# USB_PD_TYPE-C.net
KiCad netlist of a schematic drawn in Altium Designer
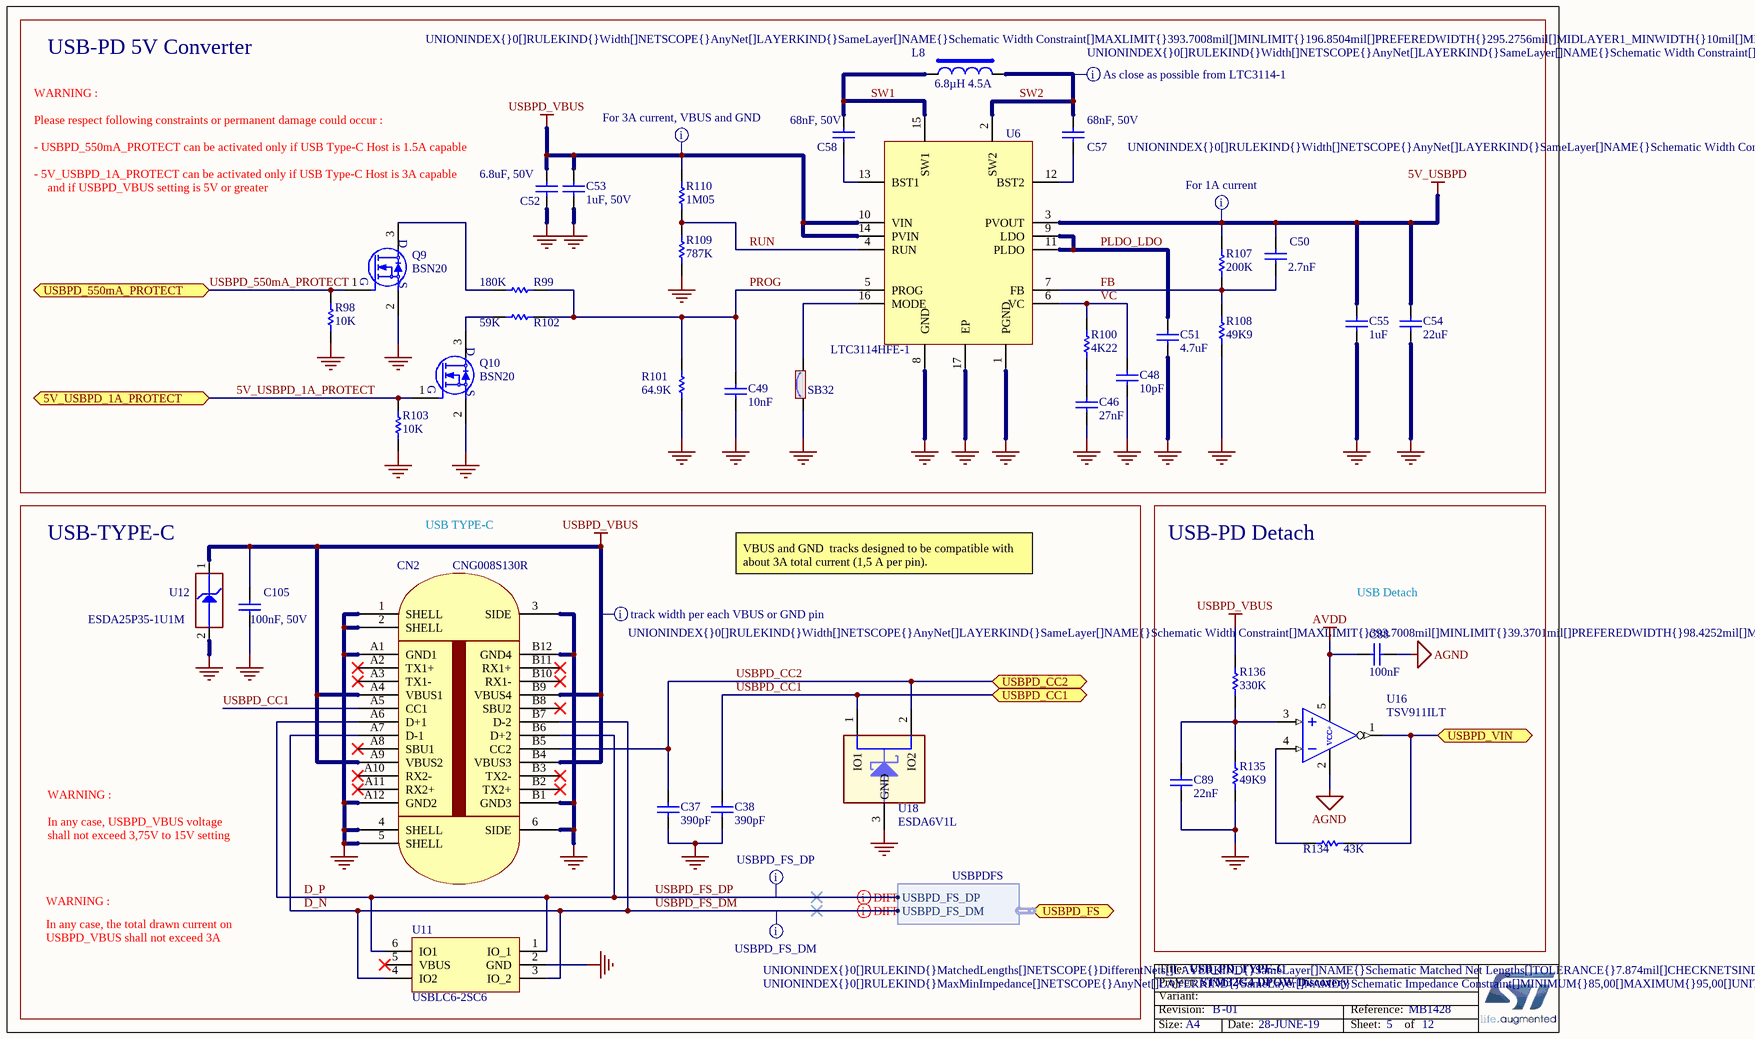
[diagram p0: USB_PD_TYPE-C.SchDoc]

(export (version "E")
  (design (tool "Eeschema 10.0.6"))
  (components
    (comp (ref "C37")
      (value "390pF")
      (footprint "C0402")
      (description "Capacitor, MLCC, 390pF, 50V, NPO, 5%, 0402, T=0,5mm")
      (fields
        (field (name "INTERNAL_PART_NUMBER") "MCD-01597")
        (field (name "MANUFACTURER_PART_NUMBER") "CC0402JRNPO9BN391")
        (field (name "PROVIDED_BY") "SUBCO")
      )
      (libsource (lib "MCD_PARTS_database") (part "Capacitor"))
    )
    (comp (ref "C38")
      (value "390pF")
      (footprint "C0402")
      (description "Capacitor, MLCC, 390pF, 50V, NPO, 5%, 0402, T=0,5mm")
      (fields
        (field (name "INTERNAL_PART_NUMBER") "MCD-01597")
        (field (name "MANUFACTURER_PART_NUMBER") "CC0402JRNPO9BN391")
        (field (name "PROVIDED_BY") "SUBCO")
      )
      (libsource (lib "MCD_PARTS_database") (part "Capacitor"))
    )
    (comp (ref "C46")
      (value "27nF")
      (footprint "C0805_KEMET_IPC-7351_DENSITY-LEVEL-B_H1P10")
      (description "Capacitor, MLCC, 27nF, 25V, C0G, 5%, 0805, T=1.1mm")
      (fields
        (field (name "INTERNAL_PART_NUMBER") "MCD-01719")
        (field (name "MANUFACTURER_PART_NUMBER") "C0805C273J3GACTU")
      )
      (libsource (lib "MCD_PARTS_database") (part "Capacitor"))
    )
    (comp (ref "C48")
      (value "10pF")
      (footprint "C0603")
      (description "Capacitor, MLCC, 10pF, 50V, NPO, 5%, 0603, T=0,8mm")
      (fields
        (field (name "INTERNAL_PART_NUMBER") "MCD-00637")
        (field (name "MANUFACTURER_PART_NUMBER") "CC0603JRNPO9BN100")
        (field (name "PROVIDED_BY") "SUBCO")
      )
      (libsource (lib "MCD_PARTS_database") (part "Capacitor"))
    )
    (comp (ref "C49")
      (value "10nF")
      (footprint "C0603")
      (description "Capacitor, MLCC, 10nF, 16V, X7R, 10%, 0603, T=0.8mm")
      (fields
        (field (name "INTERNAL_PART_NUMBER") "MCD-01007")
        (field (name "MANUFACTURER_PART_NUMBER") "CC0603KRX7R7BB103")
        (field (name "PROVIDED_BY") "SUBCO")
      )
      (libsource (lib "MCD_PARTS_database") (part "Capacitor"))
    )
    (comp (ref "C50")
      (value "2.7nF")
      (footprint "C0603_H0P8")
      (description "Capacitor, MLCC, 2.7nF, 16V, NPO, 5%, 0603, T=0,8mm")
      (fields
        (field (name "INTERNAL_PART_NUMBER") "MCD-01923")
        (field (name "MANUFACTURER_PART_NUMBER") "CC0603JRNPO7BN272")
        (field (name "PROVIDED_BY") "SUBCO")
      )
      (libsource (lib "MCD_PARTS_database") (part "Capacitor"))
    )
    (comp (ref "C51")
      (value "4.7uF")
      (footprint "C0603")
      (description "Capacitor, MLCC, 4.7uF, 16V, X5R, 10%, 0603, T=0.8mm")
      (fields
        (field (name "INTERNAL_PART_NUMBER") "MCD-00009")
        (field (name "MANUFACTURER_PART_NUMBER") "CC0603KRX5R7BB475")
        (field (name "PROVIDED_BY") "SUBCO")
      )
      (libsource (lib "MCD_PARTS_database") (part "Capacitor"))
    )
    (comp (ref "C52")
      (value "6.8uF, 50V")
      (footprint "C1206_H1P6")
      (description "Capacitor, MLCC, 6.8uF, 50V, X5R, 10%, 1206, T=1.6mm")
      (fields
        (field (name "INTERNAL_PART_NUMBER") "MCD-01559")
        (field (name "MANUFACTURER_PART_NUMBER") "C3216X5R1H685K160AB")
        (field (name "PROVIDED_BY") "SUBCO")
      )
      (libsource (lib "MCD_PARTS_database") (part "Capacitor"))
    )
    (comp (ref "C53")
      (value "1uF, 50V")
      (footprint "C0603_H0P8")
      (description "Capacitor,1uF,50V,X5R,10%,0603, T=0.8mm")
      (fields
        (field (name "INTERNAL_PART_NUMBER") "MCD-01703")
        (field (name "MANUFACTURER_PART_NUMBER") "CC0603KRX5R9BB105")
        (field (name "PROVIDED_BY") "SUBCO")
      )
      (libsource (lib "MCD_PARTS_database") (part "Capacitor"))
    )
    (comp (ref "C54")
      (value "22uF")
      (footprint "C1210")
      (description "Capacitor, MLCC, 22uF, 16V, 1210, X7R, 20%, T=2,5mm, ESR 2mohm@410KHz")
      (fields
        (field (name "INTERNAL_PART_NUMBER") "MCD-00614")
        (field (name "MANUFACTURER_PART_NUMBER") "GCM32ER71C226ME19")
        (field (name "PROVIDED_BY") "SUBCO")
      )
      (libsource (lib "MCD_PARTS_database") (part "Capacitor"))
    )
    (comp (ref "C55")
      (value "1uF")
      (footprint "C0603")
      (description "Capacitor, MLCC, 1uF, 16V, X5R, 10%, 0603, T=0,8mm")
      (fields
        (field (name "INTERNAL_PART_NUMBER") "MCD-00010")
        (field (name "MANUFACTURER_PART_NUMBER") "CC0603KRX5R7BB105")
        (field (name "PROVIDED_BY") "SUBCO")
      )
      (libsource (lib "MCD_PARTS_database") (part "Capacitor"))
    )
    (comp (ref "C57")
      (value "68nF, 50V")
      (footprint "C0603_H0P8")
      (description "Capacitor, MLCC, 68nF, 50V, X7R, 10%, 0603, T=0.8mm")
      (fields
        (field (name "INTERNAL_PART_NUMBER") "MCD-01667")
        (field (name "MANUFACTURER_PART_NUMBER") "CC0603KRX7R9BB683")
        (field (name "PROVIDED_BY") "SUBCO")
      )
      (libsource (lib "MCD_PARTS_database") (part "Capacitor"))
    )
    (comp (ref "C58")
      (value "68nF, 50V")
      (footprint "C0603_H0P8")
      (description "Capacitor, MLCC, 68nF, 50V, X7R, 10%, 0603, T=0.8mm")
      (fields
        (field (name "INTERNAL_PART_NUMBER") "MCD-01667")
        (field (name "MANUFACTURER_PART_NUMBER") "CC0603KRX7R9BB683")
        (field (name "PROVIDED_BY") "SUBCO")
      )
      (libsource (lib "MCD_PARTS_database") (part "Capacitor"))
    )
    (comp (ref "C88")
      (value "100nF")
      (footprint "C0402")
      (description "Capacitor, MLCC, 100nF, 16V, X7R, 10%, 0402, T=0,5mm")
      (fields
        (field (name "INTERNAL_PART_NUMBER") "MCD-00102")
        (field (name "MANUFACTURER_PART_NUMBER") "CC0402KRX7R7BB104")
        (field (name "PROVIDED_BY") "SUBCO")
      )
      (libsource (lib "MCD_PARTS_database") (part "Capacitor"))
    )
    (comp (ref "C89")
      (value "22nF")
      (footprint "C1206_H0P85")
      (description "Capacitor, COG, 22nF,50V, X7S, 5%, 1206, T=0.85mm")
      (fields
        (field (name "INTERNAL_PART_NUMBER") "MCD-01184")
        (field (name "MANUFACTURER_PART_NUMBER") "GRM3195C1H223JA01L")
        (field (name "PROVIDED_BY") "SUBCO")
      )
      (libsource (lib "MCD_PARTS_database") (part "Capacitor"))
    )
    (comp (ref "C105")
      (value "100nF, 50V")
      (footprint "C0603")
      (description "Capacitor,100nF,50V,X7R,10%,0603")
      (fields
        (field (name "INTERNAL_PART_NUMBER") "MCD-01099")
        (field (name "MANUFACTURER_PART_NUMBER") "CC0603KRX7R9BB104")
        (field (name "PROVIDED_BY") "SUBCO")
      )
      (libsource (lib "MCD_PARTS_database") (part "Capacitor"))
    )
    (comp (ref "CN2")
      (value "CNG008S130R")
      (footprint "CON_USB-TYPEC_LITKCONN-TECHNOLOGY_CNG008S130R")
      (description "USB Type C certified Connector SMT Mid-mount")
      (fields
        (field (name "INTERNAL_PART_NUMBER") "MCD-01679")
        (field (name "MANUFACTURER") "LITKCON TECHNOLOGY")
        (field (name "PROVIDED_BY") "SUBCO")
      )
      (libsource (lib "MCD_PARTS_database") (part "USB Type-C 6PTH"))
    )
    (comp (ref "L8")
      (value "6.8µH 4.5A")
      (footprint "IND_8040_WURTH_74437358068")
      (description "Inductor 6.8µH +/-20% Isat= 13.5A DCR=33.40 mOhm")
      (fields
        (field (name "INTERNAL_PART_NUMBER") "MCD-01372")
        (field (name "MANUFACTURER_PART_NUMBER") "744 373 580 68")
        (field (name "PROVIDED_BY") "SUBCO")
      )
      (libsource (lib "MCD_PARTS_database") (part "INDUCTOR_POWER"))
    )
    (comp (ref "Q9")
      (value "BSN20")
      (footprint "MOS_SOT23")
      (description "N-channel enhancement mode field-effect transistor")
      (fields
        (field (name "INTERNAL_PART_NUMBER") "MCD-00151")
        (field (name "MANUFACTURER") "NXP")
        (field (name "PROVIDED_BY") "SUBCO")
      )
      (libsource (lib "MCD_PARTS_database") (part "BSN20"))
    )
    (comp (ref "Q10")
      (value "BSN20")
      (footprint "MOS_SOT23")
      (description "N-channel enhancement mode field-effect transistor")
      (fields
        (field (name "INTERNAL_PART_NUMBER") "MCD-00151")
        (field (name "MANUFACTURER") "NXP")
        (field (name "PROVIDED_BY") "SUBCO")
      )
      (libsource (lib "MCD_PARTS_database") (part "BSN20"))
    )
    (comp (ref "R98")
      (value "10K")
      (footprint "R0603")
      (description "Resistor,10K,0603,1%,1/10W")
      (fields
        (field (name "INTERNAL_PART_NUMBER") "MCD-00220")
        (field (name "MANUFACTURER_PART_NUMBER") "RC0603FR-0710KL")
        (field (name "PROVIDED_BY") "SUBCO")
      )
      (libsource (lib "MCD_PARTS_database") (part "Resistor"))
    )
    (comp (ref "R99")
      (value "180K")
      (footprint "R0603")
      (description "Resistor,180K,0603,1%,1/10W")
      (fields
        (field (name "INTERNAL_PART_NUMBER") "MCD-00414")
        (field (name "MANUFACTURER_PART_NUMBER") "RC0603FR-07180KL")
        (field (name "PROVIDED_BY") "SUBCO")
      )
      (libsource (lib "MCD_PARTS_database") (part "Resistor"))
    )
    (comp (ref "R100")
      (value "4K22")
      (footprint "R0603_H0P45")
      (description "Resistor, 4K22, 0603, 1%, 1/10W")
      (fields
        (field (name "INTERNAL_PART_NUMBER") "MCD-01571")
        (field (name "MANUFACTURER_PART_NUMBER") "RC0603FR-074K22L")
        (field (name "PROVIDED_BY") "SUBCO")
      )
      (libsource (lib "MCD_PARTS_database") (part "Resistor"))
    )
    (comp (ref "R101")
      (value "64.9K")
      (footprint "R0603_H0P45")
      (description "Resistor, 64.9K, 0603, 1%, 1/10W")
      (fields
        (field (name "INTERNAL_PART_NUMBER") "MCD-01793")
        (field (name "MANUFACTURER_PART_NUMBER") "RC0603FR-0764K9L")
        (field (name "PROVIDED_BY") "SUBCO")
      )
      (libsource (lib "MCD_PARTS_database") (part "Resistor"))
    )
    (comp (ref "R102")
      (value "59K")
      (footprint "R0603_H0P45")
      (description "Resistor, 59K, 0603, 1%, 1/10W")
      (fields
        (field (name "INTERNAL_PART_NUMBER") "MCD-01794")
        (field (name "MANUFACTURER_PART_NUMBER") "RC0603FR-0759KL")
        (field (name "PROVIDED_BY") "SUBCO")
      )
      (libsource (lib "MCD_PARTS_database") (part "Resistor"))
    )
    (comp (ref "R103")
      (value "10K")
      (footprint "R0603")
      (description "Resistor,10K,0603,1%,1/10W")
      (fields
        (field (name "INTERNAL_PART_NUMBER") "MCD-00220")
        (field (name "MANUFACTURER_PART_NUMBER") "RC0603FR-0710KL")
        (field (name "PROVIDED_BY") "SUBCO")
      )
      (libsource (lib "MCD_PARTS_database") (part "Resistor"))
    )
    (comp (ref "R107")
      (value "200K")
      (footprint "R0603")
      (description "Resistor,200K,0603,1%,1/10W")
      (fields
        (field (name "INTERNAL_PART_NUMBER") "MCD-00424")
        (field (name "MANUFACTURER_PART_NUMBER") "RC0603FR-07200KL")
        (field (name "PROVIDED_BY") "SUBCO")
      )
      (libsource (lib "MCD_PARTS_database") (part "Resistor"))
    )
    (comp (ref "R108")
      (value "49K9")
      (footprint "R0603")
      (description "Resistor,49K9,0603,1%")
      (fields
        (field (name "INTERNAL_PART_NUMBER") "MCD-01171")
        (field (name "MANUFACTURER_PART_NUMBER") "RC0603FR-0749K9L")
        (field (name "PROVIDED_BY") "SUBCO")
      )
      (libsource (lib "MCD_PARTS_database") (part "Resistor"))
    )
    (comp (ref "R109")
      (value "787K")
      (footprint "R0603_H0P45")
      (description "Resistor, 787K, 0603, 1%, 1/10W")
      (fields
        (field (name "INTERNAL_PART_NUMBER") "MCD-01568")
        (field (name "MANUFACTURER_PART_NUMBER") "RC0603FR-07787KL")
        (field (name "PROVIDED_BY") "SUBCO")
      )
      (libsource (lib "MCD_PARTS_database") (part "Resistor"))
    )
    (comp (ref "R110")
      (value "1M05")
      (footprint "R0603_H0P45")
      (description "Resistor, 1M05, 0603, 1%, 1/10W")
      (fields
        (field (name "INTERNAL_PART_NUMBER") "MCD-01569")
        (field (name "MANUFACTURER_PART_NUMBER") "RC0603FR-071M05L")
        (field (name "PROVIDED_BY") "SUBCO")
      )
      (libsource (lib "MCD_PARTS_database") (part "Resistor"))
    )
    (comp (ref "R134")
      (value "43K")
      (footprint "R0603")
      (description "Resistor,43K,0603,1%,1/10W")
      (fields
        (field (name "INTERNAL_PART_NUMBER") "MCD-00478")
        (field (name "MANUFACTURER_PART_NUMBER") "RC0603FR-0743KL")
        (field (name "PROVIDED_BY") "SUBCO")
      )
      (libsource (lib "MCD_PARTS_database") (part "Resistor"))
    )
    (comp (ref "R135")
      (value "49K9")
      (footprint "R0603")
      (description "Resistor,49K9,0603,1%")
      (fields
        (field (name "INTERNAL_PART_NUMBER") "MCD-01171")
        (field (name "MANUFACTURER_PART_NUMBER") "RC0603FR-0749K9L")
        (field (name "PROVIDED_BY") "SUBCO")
      )
      (libsource (lib "MCD_PARTS_database") (part "Resistor"))
    )
    (comp (ref "R136")
      (value "330K")
      (footprint "R0603")
      (description "Resistor,330K,0603,1%,1/10W")
      (fields
        (field (name "INTERNAL_PART_NUMBER") "MCD-00458")
        (field (name "MANUFACTURER_PART_NUMBER") "RC0603FR-07330KL")
        (field (name "PROVIDED_BY") "SUBCO")
      )
      (libsource (lib "MCD_PARTS_database") (part "Resistor"))
    )
    (comp (ref "SB32")
      (value "~")
      (footprint "SOLDER-BRIDGE_R0603-0R")
      (description "Solder Bridge ON")
      (fields
        (field (name "INTERNAL_PART_NUMBER") "MCD-00071")
        (field (name "MANUFACTURER_PART_NUMBER") "RC0603JR-070RL")
        (field (name "PROVIDED_BY") "SUBCO")
      )
      (libsource (lib "MCD_PARTS_database") (part "SB_ON"))
    )
    (comp (ref "U6")
      (value "LTC3114HFE-1")
      (footprint "ICC_TSOP65P640X110_HS-17N")
      (fields
        (field (name "INTERNAL_PART_NUMBER") "MCD-01593")
        (field (name "MANUFACTURER_PART_NUMBER") "LTC3114HFE-1-TRPBF")
        (field (name "MANUFACTURER") "LINEAR TECHNOLOGY")
        (field (name "PROVIDED_BY") "SUBCO")
      )
      (libsource (lib "MCD_PARTS_database") (part "LTC3114-1"))
    )
    (comp (ref "U11")
      (value "USBLC6-2SC6")
      (footprint "ESD_SOT23-6L")
      (description "Very low capacitance ESD protection")
      (fields
        (field (name "INTERNAL_PART_NUMBER") "MCD-00163")
        (field (name "MANUFACTURER") "STMICROELECTRONICS")
        (field (name "PROVIDED_BY") "SUBCO with ST control")
      )
      (libsource (lib "MCD_PARTS_database") (part "USBLC6-2SC6"))
    )
    (comp (ref "U12")
      (value "ESDA25P35-1U1M")
      (footprint "ESD_QFN1610_2N_1K_2A")
      (description "High power Transient voltage suppressor:25V/35A EOS and ESD transients protection.")
      (fields
        (field (name "INTERNAL_PART_NUMBER") "MCD-01207")
        (field (name "MANUFACTURER") "STMICROELECTRONICS")
        (field (name "PROVIDED_BY") "SUBCO with ST control")
      )
      (libsource (lib "MCD_PARTS_database") (part "ESD-TRANSIL"))
    )
    (comp (ref "U16")
      (value "TSV911ILT")
      (footprint "AOP_SOT23-5L_H1P45")
      (description "Single, dual, and quad rail to rail input/ouput 8Mhz operational amplifiers")
      (fields
        (field (name "INTERNAL_PART_NUMBER") "MCD-01192")
        (field (name "MANUFACTURER") "STMICROELECTRONICS")
        (field (name "PROVIDED_BY") "SUBCO with ST control")
      )
      (libsource (lib "MCD_PARTS_database") (part "TSV911ILT"))
    )
    (comp (ref "U18")
      (value "ESDA6V1L")
      (footprint "ESD_SOT23")
      (description "Dual Transil array ESD protection")
      (fields
        (field (name "INTERNAL_PART_NUMBER") "MCD-00255")
        (field (name "MANUFACTURER") "STMICROELECTRONICS")
        (field (name "PROVIDED_BY") "SUBCO with ST control")
      )
      (libsource (lib "MCD_PARTS_database") (part "ESDAxxL"))
    )
  )
  (nets
    (net (code "2") (name "/5V_USBPD_1A_PROTECT") (class "Default")
      (node (ref "Q10") (pin "1") (pinfunction "G_1") (pintype "passive"))
      (node (ref "R103") (pin "2") (pinfunction "2_2") (pintype "passive"))
    )
    (net (code "3") (name "/D_N") (class "Default")
      (node (ref "CN2") (pin "A7") (pinfunction "D-1_A7") (pintype "passive"))
      (node (ref "CN2") (pin "B7") (pinfunction "D-2_B7") (pintype "passive"))
      (node (ref "U11") (pin "3") (pinfunction "IO_2_3") (pintype "passive"))
      (node (ref "U11") (pin "4") (pinfunction "IO2_4") (pintype "passive"))
    )
    (net (code "4") (name "/D_P") (class "Default")
      (node (ref "CN2") (pin "A6") (pinfunction "D+1_A6") (pintype "passive"))
      (node (ref "CN2") (pin "B6") (pinfunction "D+2_B6") (pintype "passive"))
      (node (ref "U11") (pin "1") (pinfunction "IO_1_1") (pintype "passive"))
      (node (ref "U11") (pin "6") (pinfunction "IO1_6") (pintype "passive"))
    )
    (net (code "5") (name "/FB") (class "Default")
      (node (ref "C50") (pin "1") (pinfunction "1_1") (pintype "passive"))
      (node (ref "R107") (pin "1") (pinfunction "1_1") (pintype "passive"))
      (node (ref "R108") (pin "2") (pinfunction "2_2") (pintype "passive"))
      (node (ref "U6") (pin "7") (pinfunction "FB_7") (pintype "passive"))
    )
    (net (code "6") (name "/PLDO_LDO") (class "Default")
      (node (ref "C51") (pin "1") (pinfunction "1_1") (pintype "passive"))
      (node (ref "U6") (pin "11") (pinfunction "PLDO_11") (pintype "passive"))
      (node (ref "U6") (pin "9") (pinfunction "LDO_9") (pintype "passive"))
    )
    (net (code "7") (name "/PROG") (class "Default")
      (node (ref "C49") (pin "2") (pinfunction "2_2") (pintype "passive"))
      (node (ref "R101") (pin "2") (pinfunction "2_2") (pintype "passive"))
      (node (ref "R102") (pin "2") (pinfunction "2_2") (pintype "passive"))
      (node (ref "R99") (pin "2") (pinfunction "2_2") (pintype "passive"))
      (node (ref "U6") (pin "5") (pinfunction "PROG_5") (pintype "passive"))
    )
    (net (code "8") (name "/RUN") (class "Default")
      (node (ref "R109") (pin "2") (pinfunction "2_2") (pintype "passive"))
      (node (ref "R110") (pin "1") (pinfunction "1_1") (pintype "passive"))
      (node (ref "U6") (pin "4") (pinfunction "RUN_4") (pintype "passive"))
    )
    (net (code "9") (name "/SW1") (class "Default")
      (node (ref "C58") (pin "2") (pinfunction "2_2") (pintype "passive"))
      (node (ref "L8") (pin "1") (pinfunction "1_1") (pintype "passive"))
      (node (ref "U6") (pin "15") (pinfunction "SW1_15") (pintype "passive"))
    )
    (net (code "10") (name "/SW2") (class "Default")
      (node (ref "C57") (pin "2") (pinfunction "2_2") (pintype "passive"))
      (node (ref "L8") (pin "2") (pinfunction "2_2") (pintype "passive"))
      (node (ref "U6") (pin "2") (pinfunction "SW2_2") (pintype "passive"))
    )
    (net (code "11") (name "/USBPD_550mA_PROTECT") (class "Default")
      (node (ref "Q9") (pin "1") (pinfunction "G_1") (pintype "passive"))
      (node (ref "R98") (pin "2") (pinfunction "2_2") (pintype "passive"))
    )
    (net (code "12") (name "/USBPD_CC1") (class "Default")
      (node (ref "C38") (pin "2") (pinfunction "2_2") (pintype "passive"))
      (node (ref "CN2") (pin "A5") (pinfunction "CC1_A5") (pintype "passive"))
      (node (ref "U18") (pin "1") (pinfunction "IO1_1") (pintype "passive"))
    )
    (net (code "13") (name "/USBPD_CC2") (class "Default")
      (node (ref "C37") (pin "2") (pinfunction "2_2") (pintype "passive"))
      (node (ref "CN2") (pin "B5") (pinfunction "CC2_B5") (pintype "passive"))
      (node (ref "U18") (pin "2") (pinfunction "IO2_2") (pintype "passive"))
    )
    (net (code "14") (name "/USBPD_VIN") (class "Default")
      (node (ref "R134") (pin "2") (pinfunction "2_2") (pintype "passive"))
      (node (ref "U16") (pin "1") (pinfunction "OUT_1") (pintype "output"))
    )
    (net (code "15") (name "/VC") (class "Default")
      (node (ref "C48") (pin "2") (pinfunction "2_2") (pintype "passive"))
      (node (ref "R100") (pin "2") (pinfunction "2_2") (pintype "passive"))
      (node (ref "U6") (pin "6") (pinfunction "VC_6") (pintype "passive"))
    )
    (net (code "17") (name "5V_USBPD") (class "Default")
      (node (ref "C50") (pin "2") (pinfunction "2_2") (pintype "passive"))
      (node (ref "C54") (pin "2") (pinfunction "2_2") (pintype "passive"))
      (node (ref "C55") (pin "2") (pinfunction "2_2") (pintype "passive"))
      (node (ref "R107") (pin "2") (pinfunction "2_2") (pintype "passive"))
      (node (ref "U6") (pin "3") (pinfunction "PVOUT_3") (pintype "passive"))
    )
    (net (code "18") (name "AGND") (class "Default")
      (node (ref "C88") (pin "1") (pinfunction "1_1") (pintype "passive"))
      (node (ref "U16") (pin "2") (pinfunction "VCC-_2") (pintype "passive"))
    )
    (net (code "19") (name "AVDD") (class "Default")
      (node (ref "C88") (pin "2") (pinfunction "2_2") (pintype "passive"))
      (node (ref "U16") (pin "5") (pinfunction "VCC+_5") (pintype "passive"))
    )
    (net (code "20") (name "GND") (class "Default")
      (node (ref "C105") (pin "1") (pinfunction "1_1") (pintype "passive"))
      (node (ref "C37") (pin "1") (pinfunction "1_1") (pintype "passive"))
      (node (ref "C38") (pin "1") (pinfunction "1_1") (pintype "passive"))
      (node (ref "C46") (pin "1") (pinfunction "1_1") (pintype "passive"))
      (node (ref "C48") (pin "1") (pinfunction "1_1") (pintype "passive"))
      (node (ref "C49") (pin "1") (pinfunction "1_1") (pintype "passive"))
      (node (ref "C51") (pin "2") (pinfunction "2_2") (pintype "passive"))
      (node (ref "C52") (pin "1") (pinfunction "1_1") (pintype "passive"))
      (node (ref "C53") (pin "1") (pinfunction "1_1") (pintype "passive"))
      (node (ref "C54") (pin "1") (pinfunction "1_1") (pintype "passive"))
      (node (ref "C55") (pin "1") (pinfunction "1_1") (pintype "passive"))
      (node (ref "C89") (pin "1") (pinfunction "1_1") (pintype "passive"))
      (node (ref "CN2") (pin "1") (pinfunction "SHELL_1") (pintype "passive"))
      (node (ref "CN2") (pin "2") (pinfunction "SHELL_2") (pintype "passive"))
      (node (ref "CN2") (pin "3") (pinfunction "SIDE_3") (pintype "passive"))
      (node (ref "CN2") (pin "4") (pinfunction "SHELL_4") (pintype "passive"))
      (node (ref "CN2") (pin "5") (pinfunction "SHELL_5") (pintype "passive"))
      (node (ref "CN2") (pin "6") (pinfunction "SIDE_6") (pintype "passive"))
      (node (ref "CN2") (pin "A1") (pinfunction "GND1_A1") (pintype "passive"))
      (node (ref "CN2") (pin "A12") (pinfunction "GND2_A12") (pintype "passive"))
      (node (ref "CN2") (pin "B1") (pinfunction "GND3_B1") (pintype "passive"))
      (node (ref "CN2") (pin "B12") (pinfunction "GND4_B12") (pintype "passive"))
      (node (ref "Q10") (pin "2") (pinfunction "S_2") (pintype "passive"))
      (node (ref "Q9") (pin "2") (pinfunction "S_2") (pintype "passive"))
      (node (ref "R101") (pin "1") (pinfunction "1_1") (pintype "passive"))
      (node (ref "R103") (pin "1") (pinfunction "1_1") (pintype "passive"))
      (node (ref "R108") (pin "1") (pinfunction "1_1") (pintype "passive"))
      (node (ref "R109") (pin "1") (pinfunction "1_1") (pintype "passive"))
      (node (ref "R135") (pin "1") (pinfunction "1_1") (pintype "passive"))
      (node (ref "R98") (pin "1") (pinfunction "1_1") (pintype "passive"))
      (node (ref "SB32") (pin "1") (pinfunction "1_1") (pintype "passive"))
      (node (ref "U11") (pin "2") (pinfunction "GND_2") (pintype "passive"))
      (node (ref "U12") (pin "2") (pinfunction "GND_2") (pintype "passive"))
      (node (ref "U18") (pin "3") (pinfunction "GND_3") (pintype "passive"))
      (node (ref "U6") (pin "1") (pinfunction "PGND_1") (pintype "passive"))
      (node (ref "U6") (pin "17") (pinfunction "EP_17") (pintype "passive"))
      (node (ref "U6") (pin "8") (pinfunction "GND_8") (pintype "passive"))
    )
    (net (code "21") (name "Net-(C46-Pad2)") (class "Default")
      (node (ref "C46") (pin "2") (pinfunction "2_2") (pintype "passive"))
      (node (ref "R100") (pin "1") (pinfunction "1_1") (pintype "passive"))
    )
    (net (code "22") (name "Net-(Q9-D)") (class "Default")
      (node (ref "Q9") (pin "3") (pinfunction "D_3") (pintype "passive"))
      (node (ref "R99") (pin "1") (pinfunction "1_1") (pintype "passive"))
    )
    (net (code "23") (name "Net-(Q10-D)") (class "Default")
      (node (ref "Q10") (pin "3") (pinfunction "D_3") (pintype "passive"))
      (node (ref "R102") (pin "1") (pinfunction "1_1") (pintype "passive"))
    )
    (net (code "24") (name "Net-(U6-BST1)") (class "Default")
      (node (ref "C58") (pin "1") (pinfunction "1_1") (pintype "passive"))
      (node (ref "U6") (pin "13") (pinfunction "BST1_13") (pintype "passive"))
    )
    (net (code "25") (name "Net-(U6-BST2)") (class "Default")
      (node (ref "C57") (pin "1") (pinfunction "1_1") (pintype "passive"))
      (node (ref "U6") (pin "12") (pinfunction "BST2_12") (pintype "passive"))
    )
    (net (code "26") (name "Net-(U6-MODE)") (class "Default")
      (node (ref "SB32") (pin "2") (pinfunction "2_2") (pintype "passive"))
      (node (ref "U6") (pin "16") (pinfunction "MODE_16") (pintype "passive"))
    )
    (net (code "27") (name "Net-(U16-IN+)") (class "Default")
      (node (ref "C89") (pin "2") (pinfunction "2_2") (pintype "passive"))
      (node (ref "R135") (pin "2") (pinfunction "2_2") (pintype "passive"))
      (node (ref "R136") (pin "1") (pinfunction "1_1") (pintype "passive"))
      (node (ref "U16") (pin "3") (pinfunction "IN+_3") (pintype "input"))
    )
    (net (code "28") (name "Net-(U16-IN-)") (class "Default")
      (node (ref "R134") (pin "1") (pinfunction "1_1") (pintype "passive"))
      (node (ref "U16") (pin "4") (pinfunction "IN-_4") (pintype "input"))
    )
    (net (code "29") (name "USBPD_VBUS") (class "Default")
      (node (ref "C105") (pin "2") (pinfunction "2_2") (pintype "passive"))
      (node (ref "C52") (pin "2") (pinfunction "2_2") (pintype "passive"))
      (node (ref "C53") (pin "2") (pinfunction "2_2") (pintype "passive"))
      (node (ref "CN2") (pin "A4") (pinfunction "VBUS1_A4") (pintype "passive"))
      (node (ref "CN2") (pin "A9") (pinfunction "VBUS2_A9") (pintype "passive"))
      (node (ref "CN2") (pin "B4") (pinfunction "VBUS3_B4") (pintype "passive"))
      (node (ref "CN2") (pin "B9") (pinfunction "VBUS4_B9") (pintype "passive"))
      (node (ref "R110") (pin "2") (pinfunction "2_2") (pintype "passive"))
      (node (ref "R136") (pin "2") (pinfunction "2_2") (pintype "passive"))
      (node (ref "U12") (pin "1") (pinfunction "IO1_1") (pintype "passive"))
      (node (ref "U6") (pin "10") (pinfunction "VIN_10") (pintype "passive"))
      (node (ref "U6") (pin "14") (pinfunction "PVIN_14") (pintype "passive"))
    )
    (net (code "30") (name "unconnected-(CN2-RX1+-PadB11)") (class "Default")
      (node (ref "CN2") (pin "B11") (pinfunction "RX1+_B11") (pintype "passive+no_connect"))
    )
    (net (code "31") (name "unconnected-(CN2-RX1--PadB10)") (class "Default")
      (node (ref "CN2") (pin "B10") (pinfunction "RX1-_B10") (pintype "passive+no_connect"))
    )
    (net (code "32") (name "unconnected-(CN2-RX2+-PadA11)") (class "Default")
      (node (ref "CN2") (pin "A11") (pinfunction "RX2+_A11") (pintype "passive+no_connect"))
    )
    (net (code "33") (name "unconnected-(CN2-RX2--PadA10)") (class "Default")
      (node (ref "CN2") (pin "A10") (pinfunction "RX2-_A10") (pintype "passive+no_connect"))
    )
    (net (code "34") (name "unconnected-(CN2-SBU1-PadA8)") (class "Default")
      (node (ref "CN2") (pin "A8") (pinfunction "SBU1_A8") (pintype "passive+no_connect"))
    )
    (net (code "35") (name "unconnected-(CN2-SBU2-PadB8)") (class "Default")
      (node (ref "CN2") (pin "B8") (pinfunction "SBU2_B8") (pintype "passive+no_connect"))
    )
    (net (code "36") (name "unconnected-(CN2-TX1+-PadA2)") (class "Default")
      (node (ref "CN2") (pin "A2") (pinfunction "TX1+_A2") (pintype "passive+no_connect"))
    )
    (net (code "37") (name "unconnected-(CN2-TX1--PadA3)") (class "Default")
      (node (ref "CN2") (pin "A3") (pinfunction "TX1-_A3") (pintype "passive+no_connect"))
    )
    (net (code "38") (name "unconnected-(CN2-TX2+-PadB2)") (class "Default")
      (node (ref "CN2") (pin "B2") (pinfunction "TX2+_B2") (pintype "passive+no_connect"))
    )
    (net (code "39") (name "unconnected-(CN2-TX2--PadB3)") (class "Default")
      (node (ref "CN2") (pin "B3") (pinfunction "TX2-_B3") (pintype "passive+no_connect"))
    )
    (net (code "40") (name "unconnected-(U11-VBUS-Pad5)") (class "Default")
      (node (ref "U11") (pin "5") (pinfunction "VBUS_5") (pintype "passive+no_connect"))
    )
    (net (code "41") (name "unconnected-(U16-NC-Pad1)") (class "Default")
      (node (ref "U16") (pin "1") (pinfunction "NC_1") (pintype "passive"))
    )
  )
)
